# 5V5_Supply.net
KiCad netlist of a schematic drawn in Altium Designer
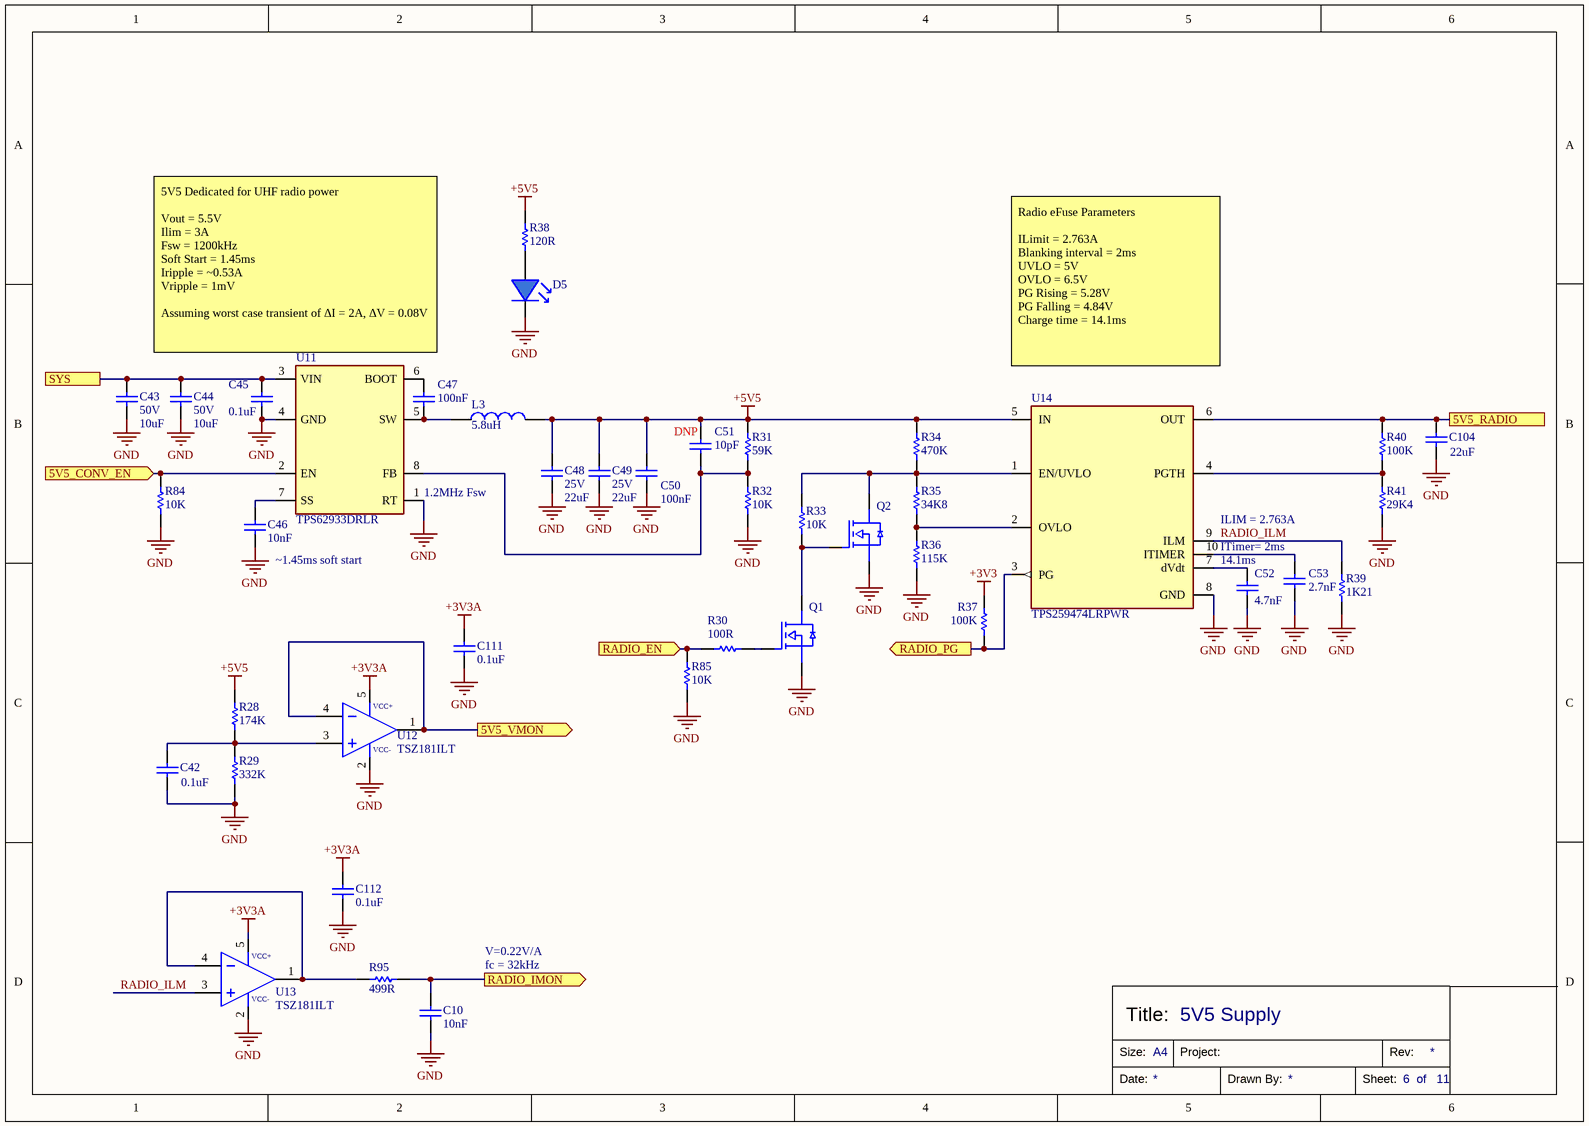
[diagram p0: 5V5_Supply.SchDoc]

(export (version "E")
  (design (tool "Eeschema 10.0.6"))
  (components
    (comp (ref "C10")
      (value "CL21B103KBANNNC")
      (footprint "CAPC0805X060")
      (description "10nF ±10% 50V Ceramic Capacitor X7R 0805 (2012 Metric)")
      (fields
        (field (name "DISTRIBUTOR PART NUMBER") "1276-1015-1-ND")
        (field (name "TOLERANCE") "10%")
        (field (name "CAPACITANCE") "10nF")
      )
      (libsource (lib "Ahristi_Library") (part "CL21B103KBANNNC"))
    )
    (comp (ref "C42")
      (value "CL21B104KACNNNC")
      (footprint "CAPC0805X060")
      (description "0.1uF ±10% 25V Ceramic Capacitor X7R 0805 (2012 Metric)")
      (fields
        (field (name "DISTRIBUTOR PART NUMBER") "1276-1099-1-ND")
        (field (name "TOLERANCE") "10%")
        (field (name "CAPACITANCE") "0.1uF")
      )
      (libsource (lib "Ahristi_Library") (part "CL21B104KACNNNC"))
    )
    (comp (ref "C43")
      (value "CL32B106KBJNNNE")
      (footprint "CAPC1210X090")
      (description "10 µF ±10% 50V Ceramic Capacitor X7R 1210 (3225 Metric)")
      (fields
        (field (name "DISTRIBUTOR PART NUMBER") "1276-3387-1-ND")
        (field (name "TOLERANCE") "10%")
        (field (name "VOLTAGE RATING") "50V")
        (field (name "CAPACITANCE") "10uF")
      )
      (libsource (lib "Ahristi_Library") (part "CL32B106KBJNNNE"))
    )
    (comp (ref "C44")
      (value "CL32B106KBJNNNE")
      (footprint "CAPC1210X090")
      (description "10 µF ±10% 50V Ceramic Capacitor X7R 1210 (3225 Metric)")
      (fields
        (field (name "DISTRIBUTOR PART NUMBER") "1276-3387-1-ND")
        (field (name "TOLERANCE") "10%")
        (field (name "VOLTAGE RATING") "50V")
        (field (name "CAPACITANCE") "10uF")
      )
      (libsource (lib "Ahristi_Library") (part "CL32B106KBJNNNE"))
    )
    (comp (ref "C45")
      (value "CL05B104KB5NNNC")
      (footprint "CAPC0402X020")
      (description "0.1 µF ±10% 50V Ceramic Capacitor X7R 0402 (1005 Metric)")
      (fields
        (field (name "TOLERANCE") "10%")
        (field (name "DISTRIBUTOR PART NUMBER") "1276-CL05B104KB5NNNCCT-ND")
        (field (name "CAPACITANCE") "0.1uF")
      )
      (libsource (lib "Ahristi_Library") (part "CL05B104KB5NNNC"))
    )
    (comp (ref "C46")
      (value "CL21B103KBANNNC")
      (footprint "CAPC0805X060")
      (description "10nF ±10% 50V Ceramic Capacitor X7R 0805 (2012 Metric)")
      (fields
        (field (name "DISTRIBUTOR PART NUMBER") "1276-1015-1-ND")
        (field (name "TOLERANCE") "10%")
        (field (name "CAPACITANCE") "10nF")
      )
      (libsource (lib "Ahristi_Library") (part "CL21B103KBANNNC"))
    )
    (comp (ref "C47")
      (value "C0603C104K5RACTU")
      (footprint "CAPC0603X040")
      (description "0.1 µF ±10% 50V Ceramic Capacitor X7R 0603 (1608 Metric)")
      (fields
        (field (name "DISTRIBUTOR PART NUMBER") "399-C0603C104K5RACTUCT-ND")
        (field (name "TOLERANCE") "10%")
        (field (name "CAPACITANCE") "100nF")
      )
      (libsource (lib "Ahristi_Library") (part "C0603C104K5RACTU"))
    )
    (comp (ref "C48")
      (value "CL32B226KAJNNNE")
      (footprint "CAPC1210X090")
      (description "22 µF ±10% 25V Ceramic Capacitor X7R 1210 (3225 Metric)")
      (fields
        (field (name "DISTRIBUTOR PART NUMBER") "1276-3392-1-ND")
        (field (name "TOLERANCE") "10%")
        (field (name "VOLTAGE RATING") "25V")
        (field (name "CAPACITANCE") "22uF")
      )
      (libsource (lib "Ahristi_Library") (part "CL32B226KAJNNNE"))
    )
    (comp (ref "C49")
      (value "CL32B226KAJNNNE")
      (footprint "CAPC1210X090")
      (description "22 µF ±10% 25V Ceramic Capacitor X7R 1210 (3225 Metric)")
      (fields
        (field (name "DISTRIBUTOR PART NUMBER") "1276-3392-1-ND")
        (field (name "TOLERANCE") "10%")
        (field (name "VOLTAGE RATING") "25V")
        (field (name "CAPACITANCE") "22uF")
      )
      (libsource (lib "Ahristi_Library") (part "CL32B226KAJNNNE"))
    )
    (comp (ref "C50")
      (value "C0603C104K5RACTU")
      (footprint "CAPC0603X040")
      (description "0.1 µF ±10% 50V Ceramic Capacitor X7R 0603 (1608 Metric)")
      (fields
        (field (name "DISTRIBUTOR PART NUMBER") "399-C0603C104K5RACTUCT-ND")
        (field (name "TOLERANCE") "10%")
        (field (name "CAPACITANCE") "100nF")
      )
      (libsource (lib "Ahristi_Library") (part "C0603C104K5RACTU"))
    )
    (comp (ref "C51")
      (value "C0603C104K5RACTU")
      (footprint "CAPC0603X040")
      (description "10 pF ±5% 50V Ceramic Capacitor C0G, NP0 0603 (1608 Metric)")
      (fields
        (field (name "PART NUMBER") "C0603C100J5GACTU")
        (field (name "DISTRIBUTOR PART NUMBER") "399-C0603C100J5GACTUCT-ND")
        (field (name "CAPACITANCE") "10pF")
      )
      (libsource (lib "Ahristi_Library") (part "C0603C100J5GACTU"))
    )
    (comp (ref "C52")
      (value "CL21B105KAFNNNE")
      (footprint "CAPC0805X060")
      (description "4.7nF ±10% 50V Ceramic Capacitor X7R 0805 (2012 Metric)")
      (fields
        (field (name "PART NUMBER") "CL21B472KBANNNC")
        (field (name "DISTRIBUTOR PART NUMBER") "1276-1155-1-ND")
        (field (name "CAPACITANCE") "4.7nF")
      )
      (libsource (lib "Ahristi_Library") (part "CL21B472KBANNNC"))
    )
    (comp (ref "C53")
      (value "GRM2165C1H272JA01D")
      (footprint "CAPC0805X060")
      (description "2.7nF ±5% 50V Ceramic Capacitor C0G, NP0 0805 (2012 Metric)")
      (fields
        (field (name "DISTRIBUTOR PART NUMBER") "490-1630-1-ND")
        (field (name "TOLERANCE") "5%")
        (field (name "CAPACITANCE") "2.7nF")
      )
      (libsource (lib "Ahristi_Library") (part "GRM2165C1H272JA01D"))
    )
    (comp (ref "C104")
      (value "CL32B226MOJNNNE")
      (footprint "CAPC1210X090")
      (description "22 µF ±20% 16V Ceramic Capacitor X7R 1210 (3225 Metric)")
      (fields
        (field (name "DISTRIBUTOR PART NUMBER") "1276-3395-1-ND")
        (field (name "TOLERANCE") "10%")
        (field (name "CAPACITANCE") "22uF")
      )
      (libsource (lib "Ahristi_Library") (part "CL32B226MOJNNNE"))
    )
    (comp (ref "C111")
      (value "C0603C104K5RACTU")
      (footprint "CAPC0603X040")
      (description "0.1 µF ±10% 50V Ceramic Capacitor X7R 0603 (1608 Metric)")
      (fields
        (field (name "DISTRIBUTOR PART NUMBER") "399-C0603C104K5RACTUCT-ND")
        (field (name "TOLERANCE") "10%")
        (field (name "CAPACITANCE") "0.1uF")
      )
      (libsource (lib "Ahristi_Library") (part "C0603C104K5RACTU"))
    )
    (comp (ref "C112")
      (value "C0603C104K5RACTU")
      (footprint "CAPC0603X040")
      (description "0.1 µF ±10% 50V Ceramic Capacitor X7R 0603 (1608 Metric)")
      (fields
        (field (name "DISTRIBUTOR PART NUMBER") "399-C0603C104K5RACTUCT-ND")
        (field (name "TOLERANCE") "10%")
        (field (name "CAPACITANCE") "0.1uF")
      )
      (libsource (lib "Ahristi_Library") (part "C0603C104K5RACTU"))
    )
    (comp (ref "D5")
      (value "LSM0805463V")
      (footprint "LEDB_0805")
      (description "Blue 469nm LED Indication - Discrete 3V 0805 (2012 Metric)")
      (fields (field (name "DISTRIBUTOR PART NUMBER") "28-LSM0805463VCT-ND"))
      (libsource (lib "Ahristi_Library") (part "LEDB0805"))
    )
    (comp (ref "L3")
      (value "744316560")
      (footprint "744316560")
      (description "Inductor 5.6uH 4.5A Shielded 28.5mOhm SMD")
      (fields (field (name "DISTRIBUTOR PART NUMBER") "732-6183-1-ND"))
      (libsource (lib "Ahristi_Library") (part "744316560"))
    )
    (comp (ref "Q1")
      (value "T2N7002AK,LM")
      (footprint "SOT23-3 MOSFET")
      (description "N-Channel 60 V 200mA (Ta) 320mW (Ta) Surface Mount SOT-23-3")
      (fields (field (name "DISTRIBUTOR PART NUMBER") "T2N7002AKLMCT-ND"))
      (libsource (lib "Ahristi_Library") (part "T2N7002AK,LM"))
    )
    (comp (ref "Q2")
      (value "T2N7002AK,LM")
      (footprint "SOT23-3 MOSFET")
      (description "N-Channel 60 V 200mA (Ta) 320mW (Ta) Surface Mount SOT-23-3")
      (fields (field (name "DISTRIBUTOR PART NUMBER") "T2N7002AKLMCT-ND"))
      (libsource (lib "Ahristi_Library") (part "T2N7002AK,LM"))
    )
    (comp (ref "R28")
      (value "RMCF0603FT174K")
      (footprint "RESC0603")
      (description "174 kOhms ±1% 0.1W, 1/10W Chip Resistor 0603 (1608 Metric) Automotive AEC-Q200 Thick Film")
      (fields
        (field (name "TOLERANCE") "1%")
        (field (name "DISTRIBUTOR PART NUMBER") "RMCF0603FT174KCT-ND")
        (field (name "RESISTANCE") "174K")
      )
      (libsource (lib "Ahristi_Library") (part "RMCF0603FT174K"))
    )
    (comp (ref "R29")
      (value "RMCF0805FT332K")
      (footprint "RESC0805")
      (description "332 kOhms ±1% 0.125W, 1/8W Chip Resistor 0805 (2012 Metric) Automotive AEC-Q200 Thick Film")
      (fields
        (field (name "TOLERANCE") "1%")
        (field (name "DISTRIBUTOR PART NUMBER") "RMCF0805FT332KCT-ND")
        (field (name "RESISTANCE") "332K")
      )
      (libsource (lib "Ahristi_Library") (part "RMCF0805FT332K"))
    )
    (comp (ref "R30")
      (value "RMCF0805FT100R")
      (footprint "RESC0805")
      (description "100 Ohms ±1% 0.125W, 1/8W Chip Resistor 0805 (2012 Metric) Automotive AEC-Q200 Thick Film")
      (fields
        (field (name "TOLERANCE") "1%")
        (field (name "DISTRIBUTOR PART NUMBER") "RMCF0805FT100RCT-ND")
        (field (name "RESISTANCE") "100R")
      )
      (libsource (lib "Ahristi_Library") (part "RMCF0805FT100R"))
    )
    (comp (ref "R31")
      (value "RMCF0603FT59K0")
      (footprint "RESC0603")
      (description "59 kOhms ±1% 0.1W, 1/10W Chip Resistor 0603 (1608 Metric) Automotive AEC-Q200 Thick Film")
      (fields
        (field (name "TOLERANCE") "1%")
        (field (name "DISTRIBUTOR PART NUMBER") "RMCF0603FT59K0CT-ND")
        (field (name "RESISTANCE") "59K")
      )
      (libsource (lib "Ahristi_Library") (part "RMCF0603FT59K0"))
    )
    (comp (ref "R32")
      (value "RMCF0603FT10K0")
      (footprint "RESC0603")
      (description "10 kOhms ±1% 0.1W, 1/10W Chip Resistor 0603 (1608 Metric) Automotive AEC-Q200 Thick Film")
      (fields
        (field (name "TOLERANCE") "1%")
        (field (name "DISTRIBUTOR PART NUMBER") "RMCF0603FT10K0CT-ND")
        (field (name "RESISTANCE") "10K")
      )
      (libsource (lib "Ahristi_Library") (part "RMCF0603FT10K0"))
    )
    (comp (ref "R33")
      (value "RMCF0805FT10K0")
      (footprint "RESC0805")
      (description "10 kOhms ±1% 0.125W, 1/8W Chip Resistor 0805 (2012 Metric) Automotive AEC-Q200 Thick Film")
      (fields
        (field (name "TOLERANCE") "1%")
        (field (name "DISTRIBUTOR PART NUMBER") "RMCF0805FT10K0CT-ND")
        (field (name "RESISTANCE") "10K")
      )
      (libsource (lib "Ahristi_Library") (part "RMCF0805FT10K0"))
    )
    (comp (ref "R34")
      (value "RMCF0603FT470K")
      (footprint "RESC0603")
      (description "470 kOhms ±1% 0.1W, 1/10W Chip Resistor 0603 (1608 Metric) Automotive AEC-Q200 Thick Film")
      (fields
        (field (name "TOLERANCE") "1%")
        (field (name "DISTRIBUTOR PART NUMBER") "RMCF0603FT470KCT-ND")
        (field (name "RESISTANCE") "470K")
      )
      (libsource (lib "Ahristi_Library") (part "RMCF0603FT470K"))
    )
    (comp (ref "R35")
      (value "RMCF0805FT34K8")
      (footprint "RESC0805")
      (description "34.8 kOhms ±1% 0.125W, 1/8W Chip Resistor 0805 (2012 Metric) Automotive AEC-Q200 Thick Film")
      (fields
        (field (name "TOLERANCE") "1%")
        (field (name "DISTRIBUTOR PART NUMBER") "RMCF0805FT34K8CT-ND")
        (field (name "RESISTANCE") "34K8")
      )
      (libsource (lib "Ahristi_Library") (part "RMCF0805FT34K8"))
    )
    (comp (ref "R36")
      (value "RMCF0805FT115K")
      (footprint "RESC0805")
      (description "115 kOhms ±1% 0.125W, 1/8W Chip Resistor 0805 (2012 Metric) Automotive AEC-Q200 Thick Film")
      (fields
        (field (name "TOLERANCE") "1%")
        (field (name "DISTRIBUTOR PART NUMBER") "RMCF0805FT115KCT-ND")
        (field (name "RESISTANCE") "115K")
      )
      (libsource (lib "Ahristi_Library") (part "RMCF0805FT115K"))
    )
    (comp (ref "R37")
      (value "RMCF0805FG100K")
      (footprint "RESC0805")
      (description "100 kOhms ±1% 0.125W, 1/8W Chip Resistor 0805 (2012 Metric) Automotive AEC-Q200 Thick Film")
      (fields
        (field (name "TOLERANCE") "1%")
        (field (name "DISTRIBUTOR PART NUMBER") "RMCF0805FG100KCT-ND")
        (field (name "RESISTANCE") "100K")
      )
      (libsource (lib "Ahristi_Library") (part "RMCF0805FG100K"))
    )
    (comp (ref "R38")
      (value "RMCF0805FT120R")
      (footprint "RESC0805")
      (description "120 Ohms ±1% 0.125W, 1/8W Chip Resistor 0805 (2012 Metric) Automotive AEC-Q200 Thick Film")
      (fields
        (field (name "TOLERANCE") "1%")
        (field (name "DISTRIBUTOR PART NUMBER") "738-RMCF0805FT120RCT-ND")
        (field (name "RESISTANCE") "120R")
      )
      (libsource (lib "Ahristi_Library") (part "RMCF0805FT120R"))
    )
    (comp (ref "R39")
      (value "RMCF0805FT1K21")
      (footprint "RESC0805")
      (description "1.21 kOhms ±1% 0.125W, 1/8W Chip Resistor 0805 (2012 Metric) Automotive AEC-Q200 Thick Film")
      (fields
        (field (name "TOLERANCE") "1%")
        (field (name "DISTRIBUTOR PART NUMBER") "RMCF0805FT1K21CT-ND")
        (field (name "RESISTANCE") "1K21")
      )
      (libsource (lib "Ahristi_Library") (part "RMCF0805FT1K21"))
    )
    (comp (ref "R40")
      (value "RMCF0805FG100K")
      (footprint "RESC0805")
      (description "100 kOhms ±1% 0.125W, 1/8W Chip Resistor 0805 (2012 Metric) Automotive AEC-Q200 Thick Film")
      (fields
        (field (name "TOLERANCE") "1%")
        (field (name "DISTRIBUTOR PART NUMBER") "RMCF0805FG100KCT-ND")
        (field (name "RESISTANCE") "100K")
      )
      (libsource (lib "Ahristi_Library") (part "RMCF0805FG100K"))
    )
    (comp (ref "R41")
      (value "RMCF0805FT29K4")
      (footprint "RESC0805")
      (description "29.4 kOhms ±1% 0.125W, 1/8W Chip Resistor 0805 (2012 Metric) Automotive AEC-Q200 Thick Film")
      (fields
        (field (name "TOLERANCE") "1%")
        (field (name "DISTRIBUTOR PART NUMBER") "RMCF0805FT29K4CT-ND")
        (field (name "RESISTANCE") "29K4")
      )
      (libsource (lib "Ahristi_Library") (part "RMCF0805FT29K4"))
    )
    (comp (ref "R84")
      (value "RMCF0805FT10K0")
      (footprint "RESC0805")
      (description "10 kOhms ±1% 0.125W, 1/8W Chip Resistor 0805 (2012 Metric) Automotive AEC-Q200 Thick Film")
      (fields
        (field (name "TOLERANCE") "1%")
        (field (name "DISTRIBUTOR PART NUMBER") "RMCF0805FT10K0CT-ND")
        (field (name "RESISTANCE") "10K")
      )
      (libsource (lib "Ahristi_Library") (part "RMCF0805FT10K0"))
    )
    (comp (ref "R85")
      (value "RMCF0805FT10K0")
      (footprint "RESC0805")
      (description "10 kOhms ±1% 0.125W, 1/8W Chip Resistor 0805 (2012 Metric) Automotive AEC-Q200 Thick Film")
      (fields
        (field (name "TOLERANCE") "1%")
        (field (name "DISTRIBUTOR PART NUMBER") "RMCF0805FT10K0CT-ND")
        (field (name "RESISTANCE") "10K")
      )
      (libsource (lib "Ahristi_Library") (part "RMCF0805FT10K0"))
    )
    (comp (ref "R95")
      (value "RMCF0805FT499R")
      (footprint "RESC0805")
      (description "499 Ohms ±1% 0.125W, 1/8W Chip Resistor 0805 (2012 Metric) Automotive AEC-Q200 Thick Film")
      (fields
        (field (name "TOLERANCE") "1%")
        (field (name "DISTRIBUTOR PART NUMBER") "RMCF0805FT499RCT-ND")
        (field (name "RESISTANCE") "499R")
      )
      (libsource (lib "Ahristi_Library") (part "RMCF0805FT499R"))
    )
    (comp (ref "U11")
      (value "TPS62933DRLR")
      (footprint "SOT-583")
      (description "Buck Switching Regulator IC Positive Adjustable 0.8V 1 Output 3A SOT-583")
      (fields (field (name "DISTRIBUTOR PART NUMBER") "296-TPS62933DRLRCT-ND"))
      (libsource (lib "Ahristi_Library") (part "TPS62933DRLR"))
    )
    (comp (ref "U12")
      (value "TSZ181ILT")
      (footprint "SOT23-5 IC")
      (description "Operational Amplifier, General Purpose, 2.2V~5.5V")
      (fields (field (name "DISTRIBUTOR PART NUMBER") "497-18084-1-ND"))
      (libsource (lib "Ahristi_Library") (part "TSZ181ILT"))
    )
    (comp (ref "U13")
      (value "TSZ181ILT")
      (footprint "SOT23-5 IC")
      (description "Operational Amplifier, General Purpose, 2.2V~5.5V")
      (fields (field (name "DISTRIBUTOR PART NUMBER") "497-18084-1-ND"))
      (libsource (lib "Ahristi_Library") (part "TSZ181ILT"))
    )
    (comp (ref "U14")
      (value "TPS259474LRPWR")
      (footprint "VFQFN-10")
      (description "eFuse 5.5A, 2.7V~23V, 28mOhm, Reverse Current Blocking with Input Reverse Polarity Protection")
      (fields (field (name "DISTRIBUTOR PART NUMBER") "296-TPS259474LRPWRCT-ND"))
      (libsource (lib "Ahristi_Library") (part "TPS259474LRPWR"))
    )
  )
  (nets
    (net (code "1") (name "+3V3") (class "Default")
      (node (ref "R37") (pin "2") (pinfunction "2_2") (pintype "passive"))
    )
    (net (code "2") (name "+3V3A") (class "Default")
      (node (ref "C111") (pin "2") (pinfunction "2_2") (pintype "passive"))
      (node (ref "C112") (pin "2") (pinfunction "2_2") (pintype "passive"))
      (node (ref "U12") (pin "5") (pinfunction "VCC+_5") (pintype "power_in"))
      (node (ref "U13") (pin "5") (pinfunction "VCC+_5") (pintype "power_in"))
    )
    (net (code "3") (name "+5V5") (class "Default")
      (node (ref "C48") (pin "2") (pinfunction "2_2") (pintype "passive"))
      (node (ref "C49") (pin "2") (pinfunction "2_2") (pintype "passive"))
      (node (ref "C50") (pin "2") (pinfunction "2_2") (pintype "passive"))
      (node (ref "C51") (pin "2") (pinfunction "2_2") (pintype "passive"))
      (node (ref "L3") (pin "2") (pinfunction "2_2") (pintype "passive"))
      (node (ref "R28") (pin "2") (pinfunction "2_2") (pintype "passive"))
      (node (ref "R31") (pin "2") (pinfunction "2_2") (pintype "passive"))
      (node (ref "R34") (pin "2") (pinfunction "2_2") (pintype "passive"))
      (node (ref "R38") (pin "2") (pinfunction "2_2") (pintype "passive"))
      (node (ref "U14") (pin "5") (pinfunction "IN_5") (pintype "passive"))
    )
    (net (code "4") (name "/5V5_CONV_EN") (class "Default")
      (node (ref "R84") (pin "2") (pinfunction "2_2") (pintype "passive"))
      (node (ref "U11") (pin "2") (pinfunction "EN_2") (pintype "passive"))
    )
    (net (code "5") (name "/5V5_RADIO") (class "Default")
      (node (ref "C104") (pin "2") (pinfunction "2_2") (pintype "passive"))
      (node (ref "R40") (pin "2") (pinfunction "2_2") (pintype "passive"))
      (node (ref "U14") (pin "6") (pinfunction "OUT_6") (pintype "passive"))
    )
    (net (code "6") (name "/5V5_VMON") (class "Default")
      (node (ref "U12") (pin "1") (pinfunction "OUT_1") (pintype "passive"))
      (node (ref "U12") (pin "4") (pinfunction "IN-_4") (pintype "passive"))
    )
    (net (code "7") (name "/RADIO_EN") (class "Default")
      (node (ref "R30") (pin "2") (pinfunction "2_2") (pintype "passive"))
      (node (ref "R85") (pin "2") (pinfunction "2_2") (pintype "passive"))
    )
    (net (code "8") (name "/RADIO_ILM") (class "Default")
      (node (ref "R39") (pin "2") (pinfunction "2_2") (pintype "passive"))
      (node (ref "U13") (pin "3") (pinfunction "IN+_3") (pintype "passive"))
      (node (ref "U14") (pin "9") (pinfunction "ILM_9") (pintype "passive"))
    )
    (net (code "9") (name "/RADIO_IMON") (class "Default")
      (node (ref "C10") (pin "2") (pinfunction "2_2") (pintype "passive"))
      (node (ref "R95") (pin "2") (pinfunction "2_2") (pintype "passive"))
    )
    (net (code "10") (name "/RADIO_PG") (class "Default")
      (node (ref "R37") (pin "1") (pinfunction "1_1") (pintype "passive"))
      (node (ref "U14") (pin "3") (pinfunction "PG_3") (pintype "output"))
    )
    (net (code "11") (name "/SYS") (class "Default")
      (node (ref "C43") (pin "2") (pinfunction "2_2") (pintype "passive"))
      (node (ref "C44") (pin "2") (pinfunction "2_2") (pintype "passive"))
      (node (ref "C45") (pin "2") (pinfunction "2_2") (pintype "passive"))
      (node (ref "U11") (pin "3") (pinfunction "VIN_3") (pintype "passive"))
    )
    (net (code "12") (name "GND") (class "Default")
      (node (ref "C10") (pin "1") (pinfunction "1_1") (pintype "passive"))
      (node (ref "C104") (pin "1") (pinfunction "1_1") (pintype "passive"))
      (node (ref "C111") (pin "1") (pinfunction "1_1") (pintype "passive"))
      (node (ref "C112") (pin "1") (pinfunction "1_1") (pintype "passive"))
      (node (ref "C42") (pin "1") (pinfunction "1_1") (pintype "passive"))
      (node (ref "C43") (pin "1") (pinfunction "1_1") (pintype "passive"))
      (node (ref "C44") (pin "1") (pinfunction "1_1") (pintype "passive"))
      (node (ref "C45") (pin "1") (pinfunction "1_1") (pintype "passive"))
      (node (ref "C46") (pin "1") (pinfunction "1_1") (pintype "passive"))
      (node (ref "C48") (pin "1") (pinfunction "1_1") (pintype "passive"))
      (node (ref "C49") (pin "1") (pinfunction "1_1") (pintype "passive"))
      (node (ref "C50") (pin "1") (pinfunction "1_1") (pintype "passive"))
      (node (ref "C52") (pin "1") (pinfunction "1_1") (pintype "passive"))
      (node (ref "C53") (pin "1") (pinfunction "1_1") (pintype "passive"))
      (node (ref "D5") (pin "K") (pinfunction "K_K") (pintype "passive"))
      (node (ref "Q1") (pin "S") (pinfunction "S_S") (pintype "passive"))
      (node (ref "Q2") (pin "S") (pinfunction "S_S") (pintype "passive"))
      (node (ref "R29") (pin "1") (pinfunction "1_1") (pintype "passive"))
      (node (ref "R32") (pin "1") (pinfunction "1_1") (pintype "passive"))
      (node (ref "R36") (pin "1") (pinfunction "1_1") (pintype "passive"))
      (node (ref "R39") (pin "1") (pinfunction "1_1") (pintype "passive"))
      (node (ref "R41") (pin "1") (pinfunction "1_1") (pintype "passive"))
      (node (ref "R84") (pin "1") (pinfunction "1_1") (pintype "passive"))
      (node (ref "R85") (pin "1") (pinfunction "1_1") (pintype "passive"))
      (node (ref "U11") (pin "1") (pinfunction "RT_1") (pintype "passive"))
      (node (ref "U11") (pin "4") (pinfunction "GND_4") (pintype "passive"))
      (node (ref "U12") (pin "2") (pinfunction "VCC-_2") (pintype "power_in"))
      (node (ref "U13") (pin "2") (pinfunction "VCC-_2") (pintype "power_in"))
      (node (ref "U14") (pin "8") (pinfunction "GND_8") (pintype "passive"))
    )
    (net (code "13") (name "Net-(D5-PadA)") (class "Default")
      (node (ref "D5") (pin "A") (pinfunction "A_A") (pintype "passive"))
      (node (ref "R38") (pin "1") (pinfunction "1_1") (pintype "passive"))
    )
    (net (code "14") (name "Net-(Q1-PadD)") (class "Default")
      (node (ref "Q1") (pin "D") (pinfunction "D_D") (pintype "passive"))
      (node (ref "Q2") (pin "G") (pinfunction "G_G") (pintype "passive"))
      (node (ref "R33") (pin "1") (pinfunction "1_1") (pintype "passive"))
    )
    (net (code "15") (name "Net-(Q1-PadG)") (class "Default")
      (node (ref "Q1") (pin "G") (pinfunction "G_G") (pintype "passive"))
      (node (ref "R30") (pin "1") (pinfunction "1_1") (pintype "passive"))
    )
    (net (code "16") (name "Net-(U11-BOOT)") (class "Default")
      (node (ref "C47") (pin "2") (pinfunction "2_2") (pintype "passive"))
      (node (ref "U11") (pin "6") (pinfunction "BOOT_6") (pintype "passive"))
    )
    (net (code "17") (name "Net-(U11-FB)") (class "Default")
      (node (ref "C51") (pin "1") (pinfunction "1_1") (pintype "passive"))
      (node (ref "R31") (pin "1") (pinfunction "1_1") (pintype "passive"))
      (node (ref "R32") (pin "2") (pinfunction "2_2") (pintype "passive"))
      (node (ref "U11") (pin "8") (pinfunction "FB_8") (pintype "passive"))
    )
    (net (code "18") (name "Net-(U11-SS)") (class "Default")
      (node (ref "C46") (pin "2") (pinfunction "2_2") (pintype "passive"))
      (node (ref "U11") (pin "7") (pinfunction "SS_7") (pintype "passive"))
    )
    (net (code "19") (name "Net-(U11-SW)") (class "Default")
      (node (ref "C47") (pin "1") (pinfunction "1_1") (pintype "passive"))
      (node (ref "L3") (pin "1") (pinfunction "1_1") (pintype "passive"))
      (node (ref "U11") (pin "5") (pinfunction "SW_5") (pintype "passive"))
    )
    (net (code "20") (name "Net-(U12-IN+)") (class "Default")
      (node (ref "C42") (pin "2") (pinfunction "2_2") (pintype "passive"))
      (node (ref "R28") (pin "1") (pinfunction "1_1") (pintype "passive"))
      (node (ref "R29") (pin "2") (pinfunction "2_2") (pintype "passive"))
      (node (ref "U12") (pin "3") (pinfunction "IN+_3") (pintype "passive"))
    )
    (net (code "21") (name "Net-(U13-IN-)") (class "Default")
      (node (ref "R95") (pin "1") (pinfunction "1_1") (pintype "passive"))
      (node (ref "U13") (pin "1") (pinfunction "OUT_1") (pintype "passive"))
      (node (ref "U13") (pin "4") (pinfunction "IN-_4") (pintype "passive"))
    )
    (net (code "22") (name "Net-(U14-EN{slash}UVLO)") (class "Default")
      (node (ref "Q2") (pin "D") (pinfunction "D_D") (pintype "passive"))
      (node (ref "R33") (pin "2") (pinfunction "2_2") (pintype "passive"))
      (node (ref "R34") (pin "1") (pinfunction "1_1") (pintype "passive"))
      (node (ref "R35") (pin "2") (pinfunction "2_2") (pintype "passive"))
      (node (ref "U14") (pin "1") (pinfunction "EN/UVLO_1") (pintype "passive"))
    )
    (net (code "23") (name "Net-(U14-ITIMER)") (class "Default")
      (node (ref "C53") (pin "2") (pinfunction "2_2") (pintype "passive"))
      (node (ref "U14") (pin "10") (pinfunction "ITIMER_10") (pintype "passive"))
    )
    (net (code "24") (name "Net-(U14-OVLO)") (class "Default")
      (node (ref "R35") (pin "1") (pinfunction "1_1") (pintype "passive"))
      (node (ref "R36") (pin "2") (pinfunction "2_2") (pintype "passive"))
      (node (ref "U14") (pin "2") (pinfunction "OVLO_2") (pintype "passive"))
    )
    (net (code "25") (name "Net-(U14-PGTH)") (class "Default")
      (node (ref "R40") (pin "1") (pinfunction "1_1") (pintype "passive"))
      (node (ref "R41") (pin "2") (pinfunction "2_2") (pintype "passive"))
      (node (ref "U14") (pin "4") (pinfunction "PGTH_4") (pintype "passive"))
    )
    (net (code "26") (name "Net-(U14-dVdt)") (class "Default")
      (node (ref "C52") (pin "2") (pinfunction "2_2") (pintype "passive"))
      (node (ref "U14") (pin "7") (pinfunction "dVdt_7") (pintype "passive"))
    )
  )
)
